# rfm12b_board.net
KiCad netlist of a schematic drawn in EAGLE
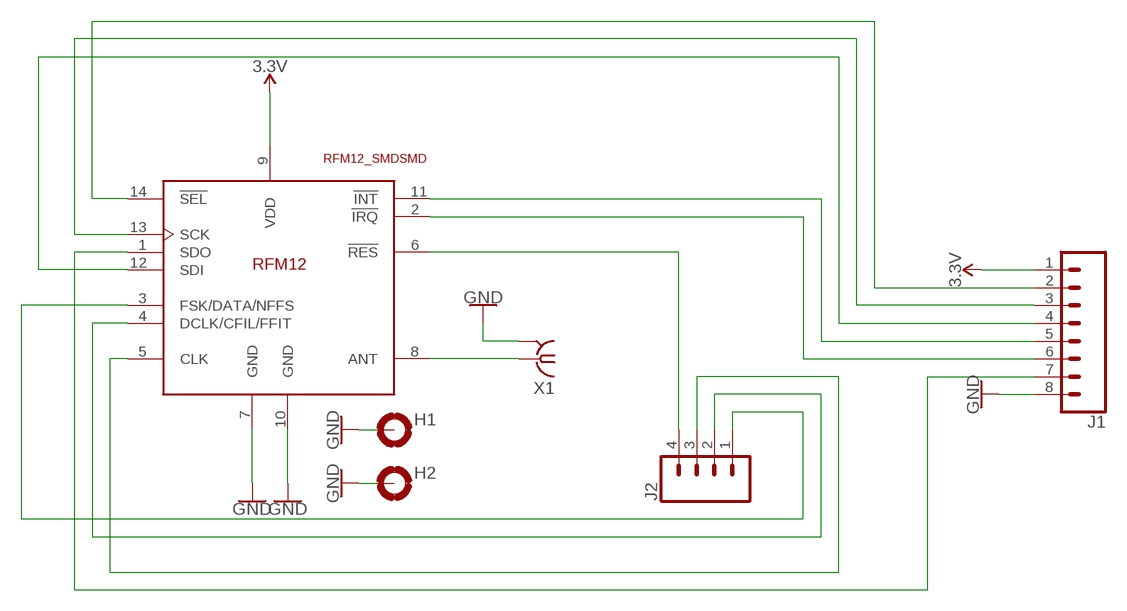
[diagram p0: schematic, sheet 1]

(export (version "E")
  (design (tool "Eeschema 10.0.6"))
  (components
    (comp (ref "H1")
      (value "MOUNT-PAD-ROUND3.0")
      (footprint "eagle-import:3,0-PAD")
      (libsource (lib "eagle-import") (part "MOUNT-PAD-ROUND3.0"))
    )
    (comp (ref "H2")
      (value "MOUNT-PAD-ROUND3.0")
      (footprint "eagle-import:3,0-PAD")
      (libsource (lib "eagle-import") (part "MOUNT-PAD-ROUND3.0"))
    )
    (comp (ref "J1")
      (value "CONN_08LONGPADS")
      (footprint "eagle-import:1X08_LONGPADS")
      (libsource (lib "eagle-import") (part "CONN_08LONGPADS"))
    )
    (comp (ref "J2")
      (value "CONN_04JST-PTH-VERT")
      (footprint "eagle-import:JST-4-PTH-VERT")
      (libsource (lib "eagle-import") (part "CONN_04JST-PTH-VERT"))
    )
    (comp (ref "U$1")
      (value "RFM12_SMDSMD")
      (footprint "eagle-import:RFM12")
      (libsource (lib "eagle-import") (part "RFM12_SMDSMD"))
    )
    (comp (ref "X1")
      (value "SMA-142-0711-821/826")
      (footprint "eagle-import:J502-ND-142-0711-821_826")
      (fields (field (name "MF") "JOHNSON COMPONENTS") (field (name "MPN") "142-0711-821"))
      (libsource (lib "eagle-import") (part "SMA-142-0711-821/826"))
    )
  )
  (nets
    (net (code "1") (name "3.3V") (class "Default")
      (node (ref "J1") (pin "1") (pinfunction "1_1") (pintype "passive"))
      (node (ref "U$1") (pin "9") (pinfunction "VDD_9") (pintype "power_in"))
    )
    (net (code "2") (name "GND") (class "Default")
      (node (ref "H1") (pin "B3,0") (pinfunction "MOUNT_B3,0") (pintype "passive"))
      (node (ref "H2") (pin "B3,0") (pinfunction "MOUNT_B3,0") (pintype "passive"))
      (node (ref "J1") (pin "8") (pinfunction "8_8") (pintype "passive"))
      (node (ref "U$1") (pin "10") (pinfunction "GND_10") (pintype "passive"))
      (node (ref "U$1") (pin "7") (pinfunction "GND_7") (pintype "passive"))
      (node (ref "X1") (pin "G@1") (pinfunction "2_G@1") (pintype "passive"))
      (node (ref "X1") (pin "G@2") (pinfunction "2_G@2") (pintype "passive"))
      (node (ref "X1") (pin "G@3") (pinfunction "2_G@3") (pintype "passive"))
      (node (ref "X1") (pin "G@4") (pinfunction "2_G@4") (pintype "passive"))
    )
    (net (code "3") (name "Net-(U$1-ANT)") (class "Default")
      (node (ref "U$1") (pin "8") (pinfunction "ANT_8") (pintype "bidirectional"))
      (node (ref "X1") (pin "1") (pinfunction "1_1") (pintype "passive"))
    )
    (net (code "4") (name "Net-(U$1-CLK)") (class "Default")
      (node (ref "J2") (pin "3") (pinfunction "3_3") (pintype "passive"))
      (node (ref "U$1") (pin "5") (pinfunction "CLK_5") (pintype "output"))
    )
    (net (code "5") (name "Net-(U$1-DCLK{slash}CFIL{slash}FFIT)") (class "Default")
      (node (ref "J2") (pin "2") (pinfunction "2_2") (pintype "passive"))
      (node (ref "U$1") (pin "4") (pinfunction "DCLK/CFIL/FFIT_4") (pintype "bidirectional"))
    )
    (net (code "6") (name "Net-(U$1-FSK{slash}DATA{slash}NFFS)") (class "Default")
      (node (ref "J2") (pin "1") (pinfunction "1_1") (pintype "passive"))
      (node (ref "U$1") (pin "3") (pinfunction "FSK/DATA/NFFS_3") (pintype "bidirectional"))
    )
    (net (code "7") (name "Net-(U$1-SCK)") (class "Default")
      (node (ref "J1") (pin "3") (pinfunction "3_3") (pintype "passive"))
      (node (ref "U$1") (pin "13") (pinfunction "SCK_13") (pintype "input"))
    )
    (net (code "8") (name "Net-(U$1-SDI)") (class "Default")
      (node (ref "J1") (pin "4") (pinfunction "4_4") (pintype "passive"))
      (node (ref "U$1") (pin "12") (pinfunction "SDI_12") (pintype "input"))
    )
    (net (code "9") (name "Net-(U$1-SDO)") (class "Default")
      (node (ref "J1") (pin "7") (pinfunction "7_7") (pintype "passive"))
      (node (ref "U$1") (pin "1") (pinfunction "SDO_1") (pintype "output"))
    )
    (net (code "10") (name "Net-(U$1-~{INT})") (class "Default")
      (node (ref "J1") (pin "5") (pinfunction "5_5") (pintype "passive"))
      (node (ref "U$1") (pin "11") (pinfunction "~{INT}_11") (pintype "bidirectional"))
    )
    (net (code "11") (name "Net-(U$1-~{IRQ})") (class "Default")
      (node (ref "J1") (pin "6") (pinfunction "6_6") (pintype "passive"))
      (node (ref "U$1") (pin "2") (pinfunction "~{IRQ}_2") (pintype "output"))
    )
    (net (code "12") (name "Net-(U$1-~{RES})") (class "Default")
      (node (ref "J2") (pin "4") (pinfunction "4_4") (pintype "passive"))
      (node (ref "U$1") (pin "6") (pinfunction "~{RES}_6") (pintype "bidirectional"))
    )
    (net (code "13") (name "Net-(U$1-~{SEL})") (class "Default")
      (node (ref "J1") (pin "2") (pinfunction "2_2") (pintype "passive"))
      (node (ref "U$1") (pin "14") (pinfunction "~{SEL}_14") (pintype "input"))
    )
  )
)
